# GPS_Antenna_Test.net
KiCad netlist of a schematic drawn in EAGLE
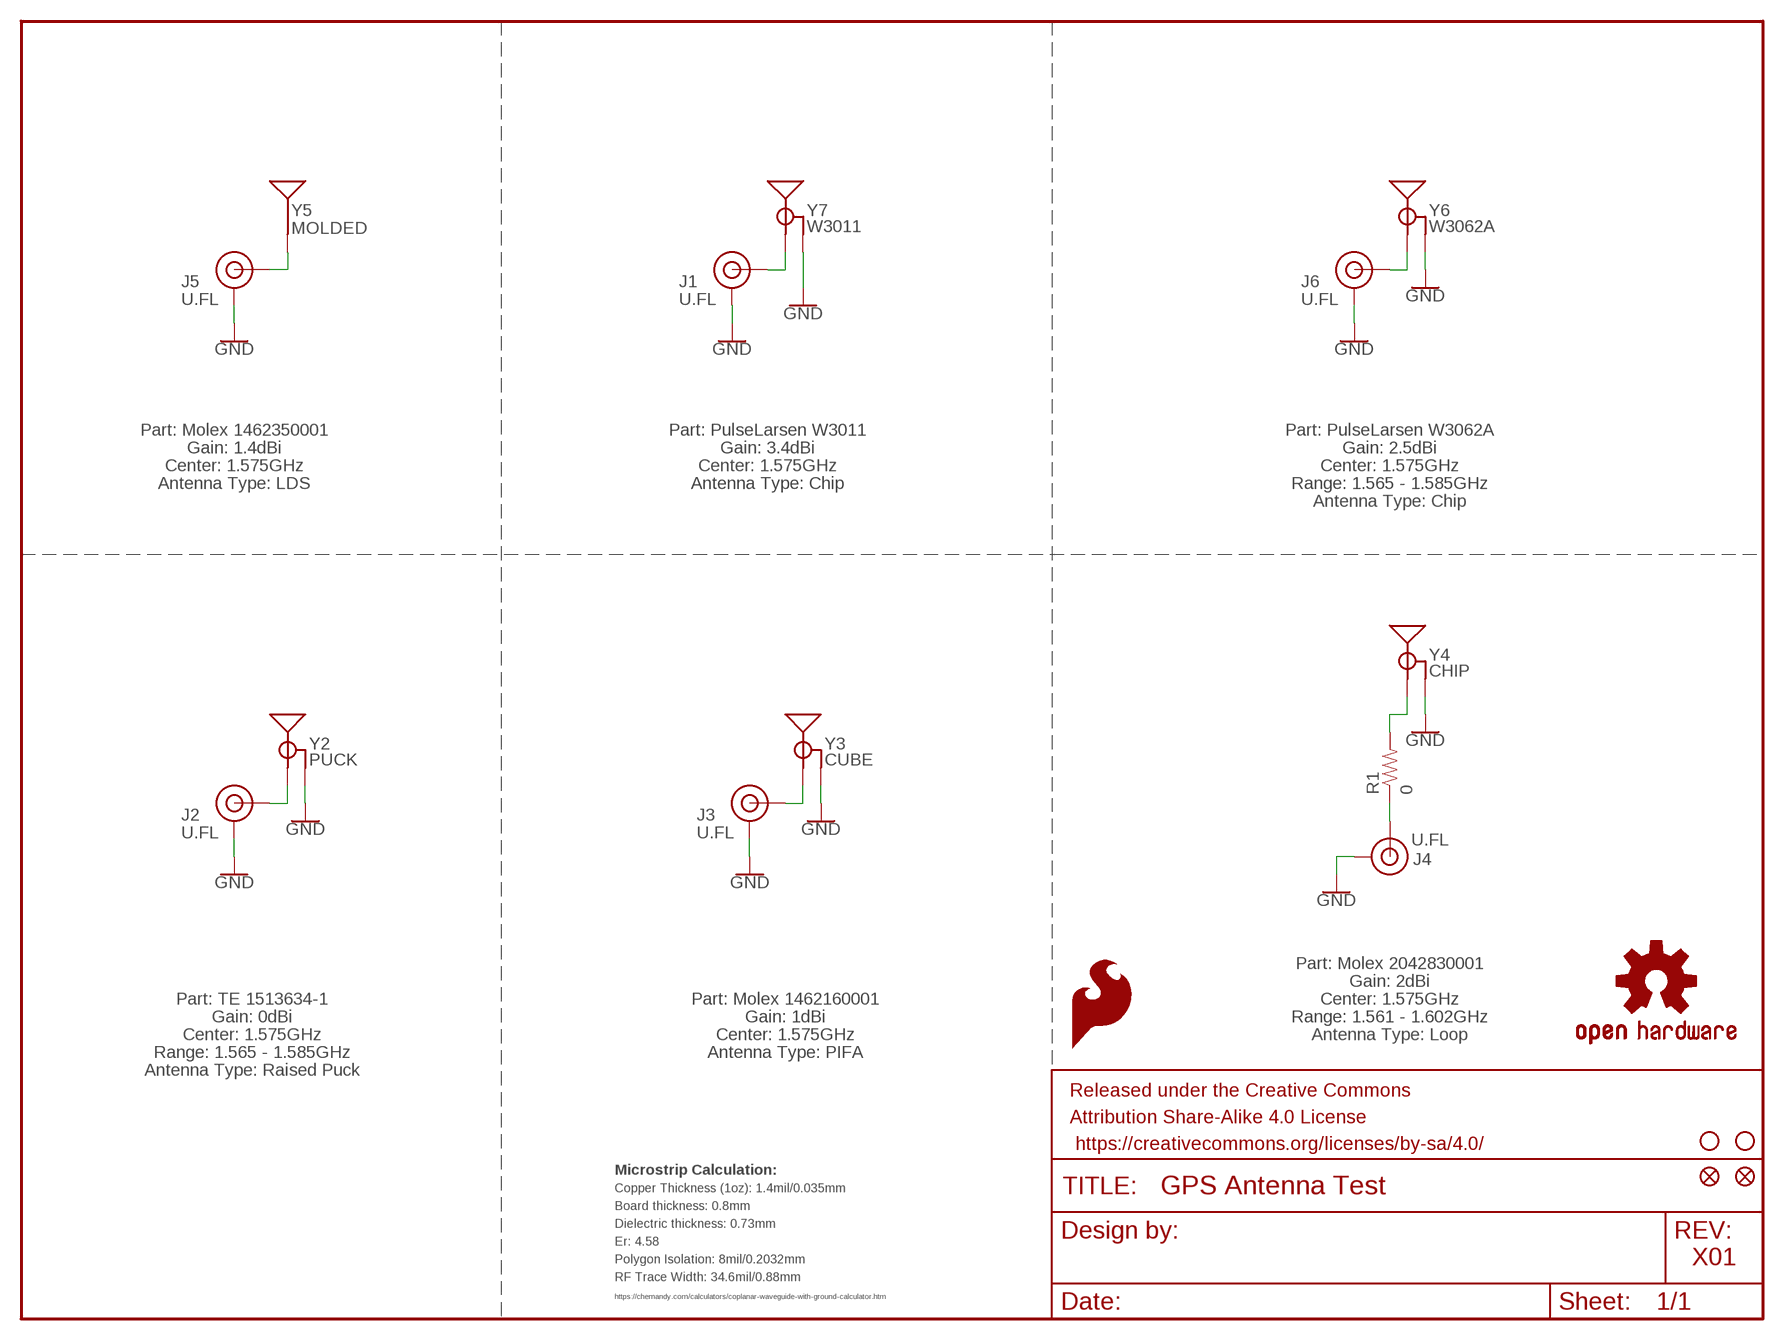
[diagram p0: schematic, sheet 1]

(export (version "E")
  (design (tool "Eeschema 10.0.6"))
  (components
    (comp (ref "FRAME1")
      (value "FRAME-LETTER")
      (footprint "eagle-import:CREATIVE_COMMONS")
      (libsource (lib "eagle-import") (part "FRAME-LETTER"))
    )
    (comp (ref "J1")
      (value "U.FL")
      (footprint "eagle-import:U.FL")
      (libsource (lib "eagle-import") (part "U.FL2PIN"))
    )
    (comp (ref "J2")
      (value "U.FL")
      (footprint "eagle-import:U.FL")
      (libsource (lib "eagle-import") (part "U.FL2PIN"))
    )
    (comp (ref "J3")
      (value "U.FL")
      (footprint "eagle-import:U.FL")
      (libsource (lib "eagle-import") (part "U.FL2PIN"))
    )
    (comp (ref "J4")
      (value "U.FL")
      (footprint "eagle-import:U.FL")
      (libsource (lib "eagle-import") (part "U.FL2PIN"))
    )
    (comp (ref "J5")
      (value "U.FL")
      (footprint "eagle-import:U.FL")
      (libsource (lib "eagle-import") (part "U.FL2PIN"))
    )
    (comp (ref "J6")
      (value "U.FL")
      (footprint "eagle-import:U.FL")
      (libsource (lib "eagle-import") (part "U.FL2PIN"))
    )
    (comp (ref "JP5")
      (value "STAND-OFF")
      (footprint "eagle-import:STAND-OFF")
      (libsource (lib "eagle-import") (part "STAND-OFF"))
    )
    (comp (ref "JP6")
      (value "STAND-OFF")
      (footprint "eagle-import:STAND-OFF")
      (libsource (lib "eagle-import") (part "STAND-OFF"))
    )
    (comp (ref "JP8")
      (value "FIDUCIAL1X2")
      (footprint "eagle-import:FIDUCIAL-1X2")
      (libsource (lib "eagle-import") (part "FIDUCIAL1X2"))
    )
    (comp (ref "JP9")
      (value "FIDUCIAL1X2")
      (footprint "eagle-import:FIDUCIAL-1X2")
      (libsource (lib "eagle-import") (part "FIDUCIAL1X2"))
    )
    (comp (ref "LOGO1")
      (value "SFE_LOGO_FLAME.1EXP")
      (footprint "eagle-import:SFE_LOGO_FLAME_COPPER_EXPOSED_.1")
      (libsource (lib "eagle-import") (part "SFE_LOGO_FLAME.1EXP"))
    )
    (comp (ref "LOGO2")
      (value "SFE_LOGO_FLAME.1EXP")
      (footprint "eagle-import:SFE_LOGO_FLAME_COPPER_EXPOSED_.1")
      (libsource (lib "eagle-import") (part "SFE_LOGO_FLAME.1EXP"))
    )
    (comp (ref "LOGO3")
      (value "SFE_LOGO_FLAME.1EXP")
      (footprint "eagle-import:SFE_LOGO_FLAME_COPPER_EXPOSED_.1")
      (libsource (lib "eagle-import") (part "SFE_LOGO_FLAME.1EXP"))
    )
    (comp (ref "LOGO4")
      (value "SFE_LOGO_FLAME.1EXP")
      (footprint "eagle-import:SFE_LOGO_FLAME_COPPER_EXPOSED_.1")
      (libsource (lib "eagle-import") (part "SFE_LOGO_FLAME.1EXP"))
    )
    (comp (ref "LOGO5")
      (value "SFE_LOGO_FLAME.1EXP")
      (footprint "eagle-import:SFE_LOGO_FLAME_COPPER_EXPOSED_.1")
      (libsource (lib "eagle-import") (part "SFE_LOGO_FLAME.1EXP"))
    )
    (comp (ref "LOGO6")
      (value "SFE_LOGO_FLAME.1EXP")
      (footprint "eagle-import:SFE_LOGO_FLAME_COPPER_EXPOSED_.1")
      (libsource (lib "eagle-import") (part "SFE_LOGO_FLAME.1EXP"))
    )
    (comp (ref "R1")
      (value "0")
      (footprint "eagle-import:0402-RES")
      (libsource (lib "eagle-import") (part "RESISTOR0402-RES"))
    )
    (comp (ref "U$16")
      (value "OSHW-LOGOS")
      (footprint "eagle-import:OSHW-LOGO-S")
      (libsource (lib "eagle-import") (part "OSHW-LOGOS"))
    )
    (comp (ref "Y2")
      (value "PUCK")
      (footprint "eagle-import:TE_PUCK")
      (libsource (lib "eagle-import") (part "GPS_CHIP_ANTENNAPUCK"))
    )
    (comp (ref "Y3")
      (value "CUBE")
      (footprint "eagle-import:MOLEX_GNSS_CUBE")
      (libsource (lib "eagle-import") (part "GPS_CHIP_ANTENNACUBE"))
    )
    (comp (ref "Y4")
      (value "CHIP")
      (footprint "eagle-import:MOLEX_GNSS_CHIP")
      (libsource (lib "eagle-import") (part "GPS_CHIP_ANTENNA2042830001"))
    )
    (comp (ref "Y5")
      (value "MOLDED")
      (footprint "eagle-import:MLOEX_GNSS_MOLDED")
      (libsource (lib "eagle-import") (part "GPS_CHIP_ANTENNA_NOGNDMOLDED"))
    )
    (comp (ref "Y6")
      (value "W3062A")
      (footprint "eagle-import:W3062A")
      (libsource (lib "eagle-import") (part "GPS_CHIP_ANTENNAW3062A"))
    )
    (comp (ref "Y7")
      (value "W3011")
      (footprint "eagle-import:W3011")
      (libsource (lib "eagle-import") (part "GPS_CHIP_ANTENNAW3011"))
    )
  )
  (nets
    (net (code "1") (name "GND") (class "Default")
      (node (ref "J1") (pin "1") (pinfunction "GND_1") (pintype "bidirectional"))
      (node (ref "J1") (pin "2") (pinfunction "GND_2") (pintype "bidirectional"))
      (node (ref "J2") (pin "1") (pinfunction "GND_1") (pintype "bidirectional"))
      (node (ref "J2") (pin "2") (pinfunction "GND_2") (pintype "bidirectional"))
      (node (ref "J3") (pin "1") (pinfunction "GND_1") (pintype "bidirectional"))
      (node (ref "J3") (pin "2") (pinfunction "GND_2") (pintype "bidirectional"))
      (node (ref "J4") (pin "1") (pinfunction "GND_1") (pintype "bidirectional"))
      (node (ref "J4") (pin "2") (pinfunction "GND_2") (pintype "bidirectional"))
      (node (ref "J5") (pin "1") (pinfunction "GND_1") (pintype "bidirectional"))
      (node (ref "J5") (pin "2") (pinfunction "GND_2") (pintype "bidirectional"))
      (node (ref "J6") (pin "1") (pinfunction "GND_1") (pintype "bidirectional"))
      (node (ref "J6") (pin "2") (pinfunction "GND_2") (pintype "bidirectional"))
      (node (ref "Y2") (pin "1") (pinfunction "GND_1") (pintype "bidirectional"))
      (node (ref "Y2") (pin "2") (pinfunction "GND_2") (pintype "bidirectional"))
      (node (ref "Y2") (pin "3") (pinfunction "GND_3") (pintype "bidirectional"))
      (node (ref "Y3") (pin "GND") (pinfunction "GND_GND") (pintype "bidirectional"))
      (node (ref "Y4") (pin "1") (pinfunction "GND_1") (pintype "bidirectional"))
      (node (ref "Y4") (pin "2") (pinfunction "GND_2") (pintype "bidirectional"))
      (node (ref "Y4") (pin "3") (pinfunction "GND_3") (pintype "bidirectional"))
      (node (ref "Y6") (pin "GND") (pinfunction "GND_GND") (pintype "bidirectional"))
      (node (ref "Y7") (pin "2") (pinfunction "GND_2") (pintype "bidirectional"))
      (node (ref "Y7") (pin "3") (pinfunction "GND_3") (pintype "bidirectional"))
    )
    (net (code "2") (name "Net-(J1-SIGNAL)") (class "Default")
      (node (ref "J1") (pin "FEED") (pinfunction "SIGNAL_FEED") (pintype "bidirectional"))
      (node (ref "Y7") (pin "1") (pinfunction "SIGNAL_1") (pintype "bidirectional"))
    )
    (net (code "3") (name "Net-(J2-SIGNAL)") (class "Default")
      (node (ref "J2") (pin "FEED") (pinfunction "SIGNAL_FEED") (pintype "bidirectional"))
      (node (ref "Y2") (pin "S") (pinfunction "SIGNAL_S") (pintype "bidirectional"))
    )
    (net (code "4") (name "Net-(J3-SIGNAL)") (class "Default")
      (node (ref "J3") (pin "FEED") (pinfunction "SIGNAL_FEED") (pintype "bidirectional"))
      (node (ref "Y3") (pin "FEED") (pinfunction "SIGNAL_FEED") (pintype "bidirectional"))
    )
    (net (code "5") (name "Net-(J4-SIGNAL)") (class "Default")
      (node (ref "J4") (pin "FEED") (pinfunction "SIGNAL_FEED") (pintype "bidirectional"))
      (node (ref "R1") (pin "1") (pinfunction "1_1") (pintype "passive"))
    )
    (net (code "6") (name "Net-(J5-SIGNAL)") (class "Default")
      (node (ref "J5") (pin "FEED") (pinfunction "SIGNAL_FEED") (pintype "bidirectional"))
      (node (ref "Y5") (pin "FEED") (pinfunction "SIGNAL_FEED") (pintype "bidirectional"))
    )
    (net (code "7") (name "Net-(J6-SIGNAL)") (class "Default")
      (node (ref "J6") (pin "FEED") (pinfunction "SIGNAL_FEED") (pintype "bidirectional"))
      (node (ref "Y6") (pin "FEED") (pinfunction "SIGNAL_FEED") (pintype "bidirectional"))
    )
    (net (code "8") (name "Net-(Y4-SIGNAL)") (class "Default")
      (node (ref "R1") (pin "2") (pinfunction "2_2") (pintype "passive"))
      (node (ref "Y4") (pin "FEED") (pinfunction "SIGNAL_FEED") (pintype "bidirectional"))
    )
  )
)
